# Top.net
KiCad netlist of a schematic drawn in Altium Designer
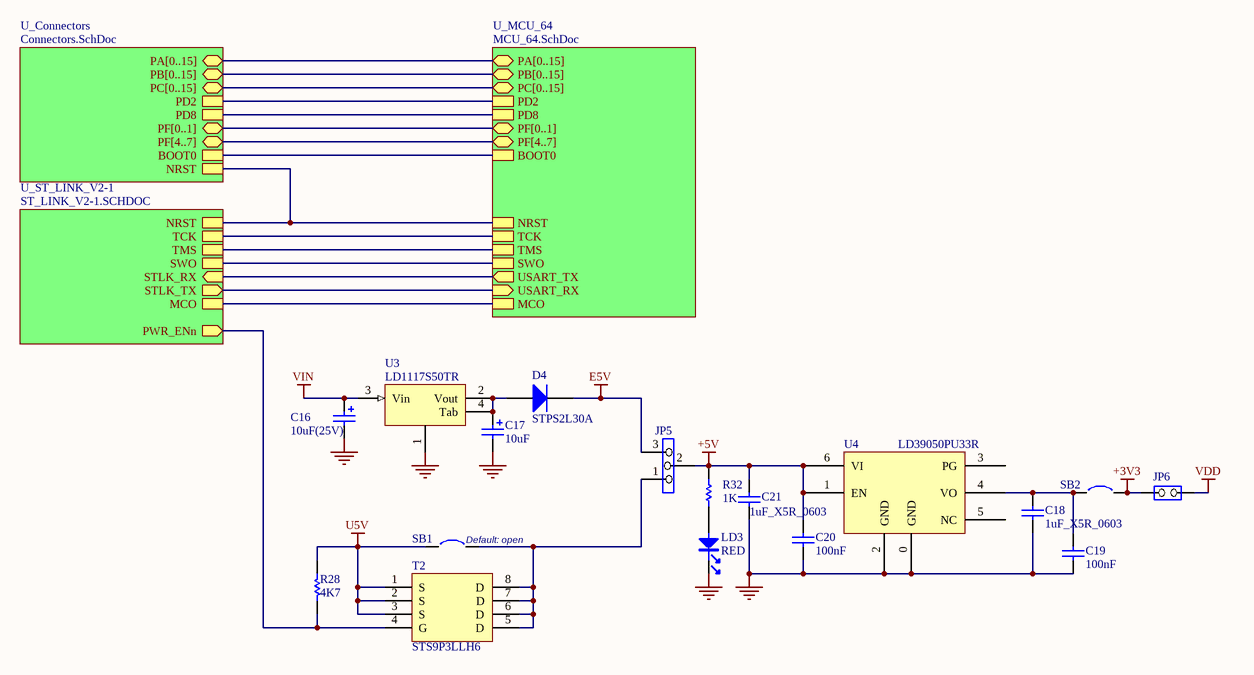
[diagram p0: Top.SchDoc]

(export (version "E")
  (design (tool "Eeschema 10.0.6"))
  (components
    (comp (ref "C16")
      (value "10uF(25V)")
      (footprint "TAN-B")
      (description "Polarized Capacitor (Radial)")
      (fields (field (name "PUBLISHER") "Altium Limited"))
      (libsource (lib "Miscellaneous Devices") (part "Cap Pol1"))
    )
    (comp (ref "C17")
      (value "10uF")
      (footprint "TAN-A")
      (description "Polarized Capacitor (Radial)")
      (fields (field (name "PUBLISHER") "Altium Limited"))
      (libsource (lib "Miscellaneous Devices") (part "Cap Pol1"))
    )
    (comp (ref "C18")
      (value "1uF_X5R_0603")
      (footprint "0603C")
      (description "0603  X5R 1µF")
      (fields (field (name "TOLERANCE") "10%"))
      (libsource (lib "MB963_1") (part "CAP SMD 0603  X5R 1µF 25V 10%"))
    )
    (comp (ref "C19")
      (value "100nF")
      (footprint "0603C")
      (description "Capacitor 0402 / 0603 / 0805")
      (libsource (lib "MCD_TOOLS") (part "Capacitor_ST"))
    )
    (comp (ref "C20")
      (value "100nF")
      (footprint "0603C")
      (description "Capacitor 0402 / 0603 / 0805")
      (libsource (lib "MCD_TOOLS") (part "Capacitor_ST"))
    )
    (comp (ref "C21")
      (value "1uF_X5R_0603")
      (footprint "0603C")
      (description "0603  X5R 1µF")
      (fields (field (name "TOLERANCE") "10%"))
      (libsource (lib "MB963_1") (part "CAP SMD 0603  X5R 1µF 25V 10%"))
    )
    (comp (ref "D4") (value "STPS2L30A") (footprint "SMA") (libsource (lib "Nucleo_64") (part "STPS2L30A")))
    (comp (ref "JP5") (value "~") (footprint "SIP3") (libsource (lib "STR910_SCHLIB") (part "Jumper3")))
    (comp (ref "JP6") (value "~") (footprint "SIP2/2.54") (libsource (lib "*") (part "JP2")))
    (comp (ref "LD3") (value "RED") (footprint "0603D") (libsource (lib "MB963_1") (part "PHOTO")))
    (comp (ref "R28")
      (value "4K7")
      (footprint "0603R")
      (description "Resistor")
      (fields (field (name "PUBLISHER") "Altium Limited"))
      (libsource (lib "*") (part "Res1"))
    )
    (comp (ref "R32")
      (value "1K")
      (footprint "0603R")
      (description "Resistor 0402 / 0603 / 0805")
      (libsource (lib "MCD_TOOLS") (part "Resistor_ST"))
    )
    (comp (ref "SB1")
      (value "Circuit Breaker")
      (footprint "JP2_SMD")
      (fields (field (name "PUBLISHER") "Altium Limited"))
      (libsource (lib "MCD_TOOLS") (part "Circuit Breaker"))
    )
    (comp (ref "SB2")
      (value "Circuit Breaker")
      (footprint "JP2_SMD")
      (fields (field (name "PUBLISHER") "Altium Limited"))
      (libsource (lib "MCD_TOOLS") (part "Circuit Breaker"))
    )
    (comp (ref "T2")
      (value "STS9P3LLH6")
      (footprint "ICC_SO8_5X4_P127")
      (description "Transistor, MOSFET, P-CH, -30V, -9A, SO-8")
      (fields
        (field (name "INTERNAL_PART_NUMBER") "MCD-02507")
        (field (name "MANUFACTURER") "STMICROELECTRONICS")
      )
      (libsource (lib "MCD_PARTS_database") (part "TRANS_P-CHANNEL_STS9P3LLH6"))
    )
    (comp (ref "U3") (value "LD1117S50TR") (footprint "SOT-223") (libsource (lib "mb1045") (part "LD1117")))
    (comp (ref "U4")
      (value "LD39050PU33R")
      (footprint "DFN6(3X3)")
      (libsource (lib "Nucleo_64") (part "LD39050P"))
    )
  )
  (nets
    (net (code "1") (name "+3V3") (class "Default")
      (node (ref "JP6") (pin "1") (pinfunction "COMMON_1") (pintype "passive"))
      (node (ref "SB2") (pin "2") (pinfunction "2_2") (pintype "passive"))
    )
    (net (code "2") (name "+5V") (class "Default")
      (node (ref "C20") (pin "2") (pinfunction "2_2") (pintype "passive"))
      (node (ref "C21") (pin "1") (pinfunction "1_1") (pintype "passive"))
      (node (ref "JP5") (pin "2") (pintype "passive"))
      (node (ref "R32") (pin "2") (pinfunction "2_2") (pintype "passive"))
      (node (ref "U4") (pin "1") (pinfunction "EN_1") (pintype "passive"))
      (node (ref "U4") (pin "6") (pinfunction "VI_6") (pintype "passive"))
    )
    (net (code "13") (name "/PWR_ENn") (class "Default")
      (node (ref "R28") (pin "2") (pinfunction "2_2") (pintype "passive"))
      (node (ref "T2") (pin "4") (pinfunction "G_4") (pintype "passive"))
    )
    (net (code "19") (name "E5V") (class "Default")
      (node (ref "D4") (pin "2") (pinfunction "K_2") (pintype "passive"))
      (node (ref "JP5") (pin "3") (pintype "passive"))
    )
    (net (code "20") (name "GND") (class "Default")
      (node (ref "C16") (pin "2") (pinfunction "2_2") (pintype "passive"))
      (node (ref "C17") (pin "2") (pinfunction "2_2") (pintype "passive"))
      (node (ref "C18") (pin "2") (pinfunction "2_2") (pintype "passive"))
      (node (ref "C19") (pin "1") (pinfunction "1_1") (pintype "passive"))
      (node (ref "C20") (pin "1") (pinfunction "1_1") (pintype "passive"))
      (node (ref "C21") (pin "2") (pinfunction "2_2") (pintype "passive"))
      (node (ref "LD3") (pin "2") (pintype "passive"))
      (node (ref "U3") (pin "1") (pintype "passive"))
      (node (ref "U4") (pin "0") (pinfunction "GND_0") (pintype "passive"))
      (node (ref "U4") (pin "2") (pinfunction "GND_2") (pintype "passive"))
    )
    (net (code "21") (name "Net-(D4-A)") (class "Default")
      (node (ref "C17") (pin "1") (pinfunction "1_1") (pintype "passive"))
      (node (ref "D4") (pin "1") (pinfunction "A_1") (pintype "passive"))
      (node (ref "U3") (pin "2") (pinfunction "Vout_2") (pintype "power_in"))
      (node (ref "U3") (pin "4") (pinfunction "Tab_4") (pintype "power_in"))
    )
    (net (code "22") (name "Net-(JP5-Pad1)") (class "Default")
      (node (ref "JP5") (pin "1") (pintype "passive"))
      (node (ref "SB1") (pin "2") (pinfunction "2_2") (pintype "passive"))
      (node (ref "T2") (pin "5") (pinfunction "D_5") (pintype "passive"))
      (node (ref "T2") (pin "6") (pinfunction "D_6") (pintype "passive"))
      (node (ref "T2") (pin "7") (pinfunction "D_7") (pintype "passive"))
      (node (ref "T2") (pin "8") (pinfunction "D_8") (pintype "passive"))
    )
    (net (code "23") (name "Net-(LD3-Pad1)") (class "Default")
      (node (ref "LD3") (pin "1") (pintype "passive"))
      (node (ref "R32") (pin "1") (pinfunction "1_1") (pintype "passive"))
    )
    (net (code "24") (name "Net-(U4-VO)") (class "Default")
      (node (ref "C18") (pin "1") (pinfunction "1_1") (pintype "passive"))
      (node (ref "C19") (pin "2") (pinfunction "2_2") (pintype "passive"))
      (node (ref "SB2") (pin "1") (pinfunction "1_1") (pintype "passive"))
      (node (ref "U4") (pin "4") (pinfunction "VO_4") (pintype "passive"))
    )
    (net (code "25") (name "U5V") (class "Default")
      (node (ref "R28") (pin "1") (pinfunction "1_1") (pintype "passive"))
      (node (ref "SB1") (pin "1") (pinfunction "1_1") (pintype "passive"))
      (node (ref "T2") (pin "1") (pinfunction "S_1") (pintype "passive"))
      (node (ref "T2") (pin "2") (pinfunction "S_2") (pintype "passive"))
      (node (ref "T2") (pin "3") (pinfunction "S_3") (pintype "passive"))
    )
    (net (code "26") (name "VDD") (class "Default")
      (node (ref "JP6") (pin "2") (pinfunction "NO_2") (pintype "passive"))
    )
    (net (code "27") (name "VIN") (class "Default")
      (node (ref "C16") (pin "1") (pinfunction "1_1") (pintype "passive"))
      (node (ref "U3") (pin "3") (pinfunction "Vin_3") (pintype "input"))
    )
    (net (code "28") (name "unconnected-(U4-NC-Pad5)") (class "Default")
      (node (ref "U4") (pin "5") (pinfunction "NC_5") (pintype "passive"))
    )
    (net (code "29") (name "unconnected-(U4-PG-Pad3)") (class "Default")
      (node (ref "U4") (pin "3") (pinfunction "PG_3") (pintype "passive"))
    )
  )
)
